# ZB1.net
KiCad netlist of a schematic drawn in Altium Designer
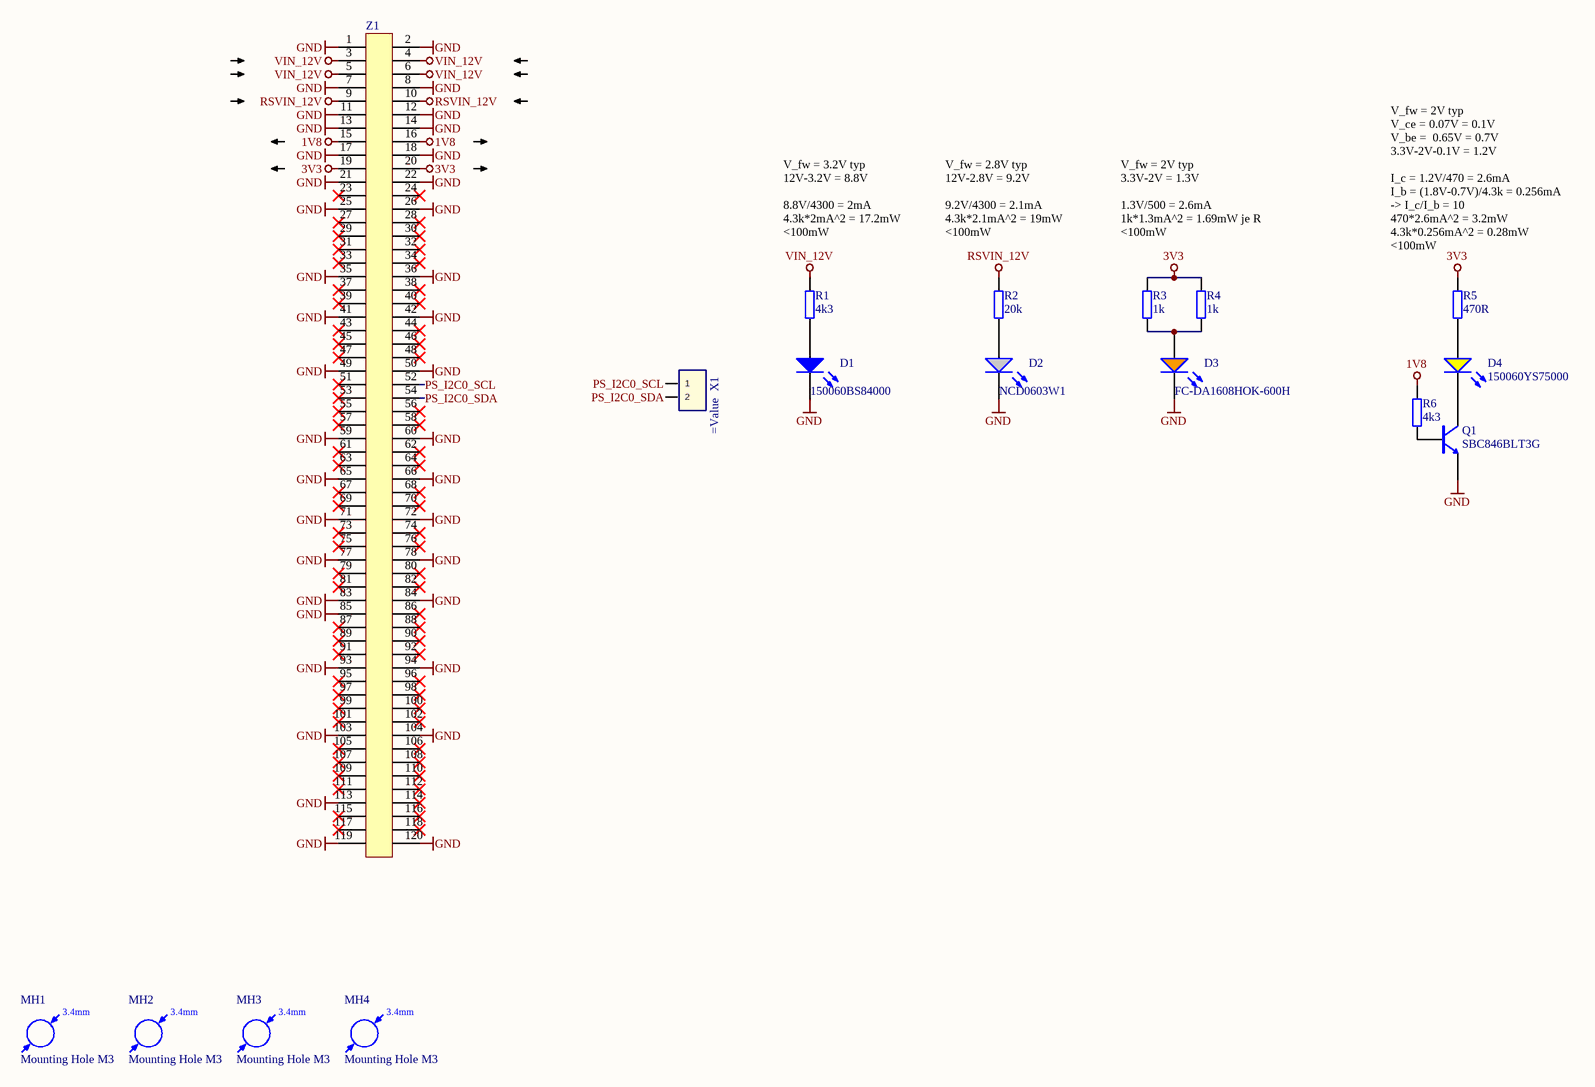
[diagram p0: ZB1.SchDoc]

(export (version "E")
  (design (tool "Eeschema 10.0.6"))
  (components
    (comp (ref "D1")
      (value "150060BS84000")
      (footprint "WL-SMCW_0603")
      (description "WL-SMCW SMD Mono-color Chip LED Waterclear Blue")
      (fields
        (field (name "MANUFACTURER") "Wuerth Elektronik")
        (field (name "LCSC PART NUMBER") "C5197644")
        (field (name "CREATED FROM") "MGremer")
      )
      (libsource (lib "user") (part "LED_Blue"))
    )
    (comp (ref "D2")
      (value "NCD0603W1")
      (footprint "WL-SMCW_0603")
      (description "White light 0603 Light Emitting Diodes (LED) ROHS")
      (fields
        (field (name "MANUFACTURER") "Foshan NationStar Optoelectronics")
        (field (name "LCSC PART NUMBER") "C84265")
        (field (name "CREATED FROM") "NDiringer")
      )
      (libsource (lib "user") (part "LED_White"))
    )
    (comp (ref "D3")
      (value "FC-DA1608HOK-600H")
      (footprint "WL-SMCW_0603")
      (description "LED ORANGE 600~610NM 80~220MCD@20MA TOP VIEW 0603 ROHS")
      (fields
        (field (name "MANUFACTURER") "Foshan NationStar Optoelectronics")
        (field (name "LCSC PART NUMBER") "C84269")
        (field (name "CREATED FROM") "T. Wendt")
      )
      (libsource (lib "user") (part "LED_Amber"))
    )
    (comp (ref "D4")
      (value "150060YS75000")
      (footprint "WL-SMCW_0603")
      (description "LED Yellow 20mA 2V 0603")
      (fields
        (field (name "MANUFACTURER") "Wuerth Elektronik")
        (field (name "LCSC PART NUMBER") "C6784997")
        (field (name "CREATED FROM") "RWeimer")
      )
      (libsource (lib "user") (part "LED_Yellow"))
    )
    (comp (ref "MH1")
      (value "Mounting Hole M3")
      (footprint "MH_3.4")
      (description "Mounting Hole")
      (fields (field (name "CREATED FROM") "MHlatky"))
      (libsource (lib "user") (part "Mounting Hole"))
    )
    (comp (ref "MH2")
      (value "Mounting Hole M3")
      (footprint "MH_3.4")
      (description "Mounting Hole")
      (fields (field (name "CREATED FROM") "MHlatky"))
      (libsource (lib "user") (part "Mounting Hole"))
    )
    (comp (ref "MH3")
      (value "Mounting Hole M3")
      (footprint "MH_3.4")
      (description "Mounting Hole")
      (fields (field (name "CREATED FROM") "MHlatky"))
      (libsource (lib "user") (part "Mounting Hole"))
    )
    (comp (ref "MH4")
      (value "Mounting Hole M3")
      (footprint "MH_3.4")
      (description "Mounting Hole")
      (fields (field (name "CREATED FROM") "MHlatky"))
      (libsource (lib "user") (part "Mounting Hole"))
    )
    (comp (ref "Q1")
      (value "SBC846BLT3G")
      (footprint "SOT-23-3_ONSC")
      (description "Bipolartransistor, NPN 100mA 80V")
      (fields
        (field (name "MANUFACTURER") "onsemi")
        (field (name "LCSC PART NUMBER") "C896883")
        (field (name "CREATED FROM") "RWeimer")
      )
      (libsource (lib "user") (part "NPN-SOT23"))
    )
    (comp (ref "R1")
      (value "4k3")
      (footprint "RES 0603_1608")
      (description "SMD resistor E24 series")
      (fields
        (field (name "MANUFACTURER PART NUMBER") "RK73B1JTTD432J")
        (field (name "MANUFACTURER") "KOA Speer")
        (field (name "CREATED FROM") "MGremer")
      )
      (libsource (lib "user") (part "Resistor"))
    )
    (comp (ref "R2")
      (value "20k")
      (footprint "RES 0603_1608")
      (description "SMD resistor E24 series")
      (fields
        (field (name "MANUFACTURER PART NUMBER") "0603WAF2002T5E")
        (field (name "MANUFACTURER") "UNI-ROYAL")
        (field (name "CREATED FROM") "AGeiger")
      )
      (libsource (lib "user") (part "Resistor"))
    )
    (comp (ref "R3")
      (value "1k")
      (footprint "RES 0603_1608")
      (description "SMD resistor E24 series")
      (fields
        (field (name "MANUFACTURER PART NUMBER") "0603WAF1001T5E")
        (field (name "MANUFACTURER") "UNI-ROYAL")
        (field (name "CREATED FROM") "AGeiger")
      )
      (libsource (lib "user") (part "Resistor"))
    )
    (comp (ref "R4")
      (value "1k")
      (footprint "RES 0603_1608")
      (description "SMD resistor E24 series")
      (fields
        (field (name "MANUFACTURER PART NUMBER") "0603WAF1001T5E")
        (field (name "MANUFACTURER") "UNI-ROYAL")
        (field (name "CREATED FROM") "AGeiger")
      )
      (libsource (lib "user") (part "Resistor"))
    )
    (comp (ref "R5")
      (value "470R")
      (footprint "RES 0603_1608")
      (description "SMD resistor E24 series")
      (fields
        (field (name "MANUFACTURER PART NUMBER") "RK73B1JTTD471J")
        (field (name "MANUFACTURER") "KOA Speer")
        (field (name "CREATED FROM") "MGremer")
      )
      (libsource (lib "user") (part "Resistor"))
    )
    (comp (ref "R6")
      (value "4k3")
      (footprint "RES 0603_1608")
      (description "SMD resistor E24 series")
      (fields
        (field (name "MANUFACTURER PART NUMBER") "RK73B1JTTD432J")
        (field (name "MANUFACTURER") "KOA Speer")
        (field (name "CREATED FROM") "MGremer")
      )
      (libsource (lib "user") (part "Resistor"))
    )
    (comp (ref "X1")
      (value "~")
      (footprint "TSW-102-XX-XXX-S")
      (description "Classic PCB Header Strips, 0.100\" pitch")
      (fields
        (field (name "MANUFACTURER") "SAMTEC")
        (field (name "LCSC PART NUMBER") "C492401")
        (field (name "CREATED BY") "May 18, 2016 - Wendy Xin")
        (field (name "CREATED FROM") "AGeiger")
      )
      (libsource (lib "user") (part "TSW-102-XX-XXX-S"))
    )
    (comp (ref "Z1")
      (value "~")
      (footprint "ERM8-060-02.0-L-DV")
      (description "0.80 mm Edge Rate Rugged High Speed")
      (fields
        (field (name "MANUFACTURER PART NUMBER") "ERM8-060-02.0-L-DV-TR")
        (field (name "MANUFACTURER") "SAMTEC")
        (field (name "CREATED FROM") "AGeiger")
      )
      (libsource (lib "user") (part "CON-120"))
    )
  )
  (nets
    (net (code "1") (name "/PS_I2C0_SCL") (class "Default")
      (node (ref "X1") (pin "1") (pinfunction "1_1") (pintype "passive"))
      (node (ref "Z1") (pin "52") (pinfunction "52_52") (pintype "passive"))
    )
    (net (code "2") (name "/PS_I2C0_SDA") (class "Default")
      (node (ref "X1") (pin "2") (pinfunction "2_2") (pintype "passive"))
      (node (ref "Z1") (pin "54") (pinfunction "54_54") (pintype "passive"))
    )
    (net (code "3") (name "1V8") (class "Default")
      (node (ref "R6") (pin "2") (pinfunction "2_2") (pintype "passive"))
      (node (ref "Z1") (pin "15") (pinfunction "15_15") (pintype "passive"))
      (node (ref "Z1") (pin "16") (pinfunction "16_16") (pintype "passive"))
    )
    (net (code "4") (name "3V3") (class "Default")
      (node (ref "R3") (pin "2") (pinfunction "2_2") (pintype "passive"))
      (node (ref "R4") (pin "2") (pinfunction "2_2") (pintype "passive"))
      (node (ref "R5") (pin "2") (pinfunction "2_2") (pintype "passive"))
      (node (ref "Z1") (pin "19") (pinfunction "19_19") (pintype "passive"))
      (node (ref "Z1") (pin "20") (pinfunction "20_20") (pintype "passive"))
    )
    (net (code "5") (name "GND") (class "Default")
      (node (ref "D1") (pin "1") (pinfunction "K_1") (pintype "passive"))
      (node (ref "D2") (pin "1") (pinfunction "K_1") (pintype "passive"))
      (node (ref "D3") (pin "1") (pinfunction "K_1") (pintype "passive"))
      (node (ref "Q1") (pin "2") (pinfunction "EMITTER_2") (pintype "passive"))
      (node (ref "Z1") (pin "1") (pinfunction "1_1") (pintype "passive"))
      (node (ref "Z1") (pin "103") (pinfunction "103_103") (pintype "passive"))
      (node (ref "Z1") (pin "104") (pinfunction "104_104") (pintype "passive"))
      (node (ref "Z1") (pin "11") (pinfunction "11_11") (pintype "passive"))
      (node (ref "Z1") (pin "113") (pinfunction "113_113") (pintype "passive"))
      (node (ref "Z1") (pin "119") (pinfunction "119_119") (pintype "passive"))
      (node (ref "Z1") (pin "12") (pinfunction "12_12") (pintype "passive"))
      (node (ref "Z1") (pin "120") (pinfunction "120_120") (pintype "passive"))
      (node (ref "Z1") (pin "13") (pinfunction "13_13") (pintype "passive"))
      (node (ref "Z1") (pin "14") (pinfunction "14_14") (pintype "passive"))
      (node (ref "Z1") (pin "17") (pinfunction "17_17") (pintype "passive"))
      (node (ref "Z1") (pin "18") (pinfunction "18_18") (pintype "passive"))
      (node (ref "Z1") (pin "2") (pinfunction "2_2") (pintype "passive"))
      (node (ref "Z1") (pin "21") (pinfunction "21_21") (pintype "passive"))
      (node (ref "Z1") (pin "22") (pinfunction "22_22") (pintype "passive"))
      (node (ref "Z1") (pin "25") (pinfunction "25_25") (pintype "passive"))
      (node (ref "Z1") (pin "26") (pinfunction "26_26") (pintype "passive"))
      (node (ref "Z1") (pin "35") (pinfunction "35_35") (pintype "passive"))
      (node (ref "Z1") (pin "36") (pinfunction "36_36") (pintype "passive"))
      (node (ref "Z1") (pin "41") (pinfunction "41_41") (pintype "passive"))
      (node (ref "Z1") (pin "42") (pinfunction "42_42") (pintype "passive"))
      (node (ref "Z1") (pin "49") (pinfunction "49_49") (pintype "passive"))
      (node (ref "Z1") (pin "50") (pinfunction "50_50") (pintype "passive"))
      (node (ref "Z1") (pin "59") (pinfunction "59_59") (pintype "passive"))
      (node (ref "Z1") (pin "60") (pinfunction "60_60") (pintype "passive"))
      (node (ref "Z1") (pin "65") (pinfunction "65_65") (pintype "passive"))
      (node (ref "Z1") (pin "66") (pinfunction "66_66") (pintype "passive"))
      (node (ref "Z1") (pin "7") (pinfunction "7_7") (pintype "passive"))
      (node (ref "Z1") (pin "71") (pinfunction "71_71") (pintype "passive"))
      (node (ref "Z1") (pin "72") (pinfunction "72_72") (pintype "passive"))
      (node (ref "Z1") (pin "77") (pinfunction "77_77") (pintype "passive"))
      (node (ref "Z1") (pin "78") (pinfunction "78_78") (pintype "passive"))
      (node (ref "Z1") (pin "8") (pinfunction "8_8") (pintype "passive"))
      (node (ref "Z1") (pin "83") (pinfunction "83_83") (pintype "passive"))
      (node (ref "Z1") (pin "84") (pinfunction "84_84") (pintype "passive"))
      (node (ref "Z1") (pin "85") (pinfunction "85_85") (pintype "passive"))
      (node (ref "Z1") (pin "93") (pinfunction "93_93") (pintype "passive"))
      (node (ref "Z1") (pin "94") (pinfunction "94_94") (pintype "passive"))
    )
    (net (code "6") (name "Net-(D1-A)") (class "Default")
      (node (ref "D1") (pin "2") (pinfunction "A_2") (pintype "passive"))
      (node (ref "R1") (pin "1") (pinfunction "1_1") (pintype "passive"))
    )
    (net (code "7") (name "Net-(D2-A)") (class "Default")
      (node (ref "D2") (pin "2") (pinfunction "A_2") (pintype "passive"))
      (node (ref "R2") (pin "1") (pinfunction "1_1") (pintype "passive"))
    )
    (net (code "8") (name "Net-(D3-A)") (class "Default")
      (node (ref "D3") (pin "2") (pinfunction "A_2") (pintype "passive"))
      (node (ref "R3") (pin "1") (pinfunction "1_1") (pintype "passive"))
      (node (ref "R4") (pin "1") (pinfunction "1_1") (pintype "passive"))
    )
    (net (code "9") (name "Net-(D4-A)") (class "Default")
      (node (ref "D4") (pin "2") (pinfunction "A_2") (pintype "passive"))
      (node (ref "R5") (pin "1") (pinfunction "1_1") (pintype "passive"))
    )
    (net (code "10") (name "Net-(D4-K)") (class "Default")
      (node (ref "D4") (pin "1") (pinfunction "K_1") (pintype "passive"))
      (node (ref "Q1") (pin "3") (pinfunction "COLLECTOR_3") (pintype "passive"))
    )
    (net (code "11") (name "Net-(Q1-BASIS)") (class "Default")
      (node (ref "Q1") (pin "1") (pinfunction "BASIS_1") (pintype "passive"))
      (node (ref "R6") (pin "1") (pinfunction "1_1") (pintype "passive"))
    )
    (net (code "12") (name "RSVIN_12V") (class "Default")
      (node (ref "R2") (pin "2") (pinfunction "2_2") (pintype "passive"))
      (node (ref "Z1") (pin "10") (pinfunction "10_10") (pintype "passive"))
      (node (ref "Z1") (pin "9") (pinfunction "9_9") (pintype "passive"))
    )
    (net (code "13") (name "VIN_12V") (class "Default")
      (node (ref "R1") (pin "2") (pinfunction "2_2") (pintype "passive"))
      (node (ref "Z1") (pin "3") (pinfunction "3_3") (pintype "passive"))
      (node (ref "Z1") (pin "4") (pinfunction "4_4") (pintype "passive"))
      (node (ref "Z1") (pin "5") (pinfunction "5_5") (pintype "passive"))
      (node (ref "Z1") (pin "6") (pinfunction "6_6") (pintype "passive"))
    )
    (net (code "14") (name "unconnected-(Z1-Pad23)") (class "Default")
      (node (ref "Z1") (pin "23") (pinfunction "23_23") (pintype "passive+no_connect"))
    )
    (net (code "15") (name "unconnected-(Z1-Pad24)") (class "Default")
      (node (ref "Z1") (pin "24") (pinfunction "24_24") (pintype "passive+no_connect"))
    )
    (net (code "16") (name "unconnected-(Z1-Pad27)") (class "Default")
      (node (ref "Z1") (pin "27") (pinfunction "27_27") (pintype "passive+no_connect"))
    )
    (net (code "17") (name "unconnected-(Z1-Pad28)") (class "Default")
      (node (ref "Z1") (pin "28") (pinfunction "28_28") (pintype "passive+no_connect"))
    )
    (net (code "18") (name "unconnected-(Z1-Pad29)") (class "Default")
      (node (ref "Z1") (pin "29") (pinfunction "29_29") (pintype "passive+no_connect"))
    )
    (net (code "19") (name "unconnected-(Z1-Pad30)") (class "Default")
      (node (ref "Z1") (pin "30") (pinfunction "30_30") (pintype "passive+no_connect"))
    )
    (net (code "20") (name "unconnected-(Z1-Pad31)") (class "Default")
      (node (ref "Z1") (pin "31") (pinfunction "31_31") (pintype "passive+no_connect"))
    )
    (net (code "21") (name "unconnected-(Z1-Pad32)") (class "Default")
      (node (ref "Z1") (pin "32") (pinfunction "32_32") (pintype "passive+no_connect"))
    )
    (net (code "22") (name "unconnected-(Z1-Pad33)") (class "Default")
      (node (ref "Z1") (pin "33") (pinfunction "33_33") (pintype "passive+no_connect"))
    )
    (net (code "23") (name "unconnected-(Z1-Pad34)") (class "Default")
      (node (ref "Z1") (pin "34") (pinfunction "34_34") (pintype "passive+no_connect"))
    )
    (net (code "24") (name "unconnected-(Z1-Pad37)") (class "Default")
      (node (ref "Z1") (pin "37") (pinfunction "37_37") (pintype "passive+no_connect"))
    )
    (net (code "25") (name "unconnected-(Z1-Pad38)") (class "Default")
      (node (ref "Z1") (pin "38") (pinfunction "38_38") (pintype "passive+no_connect"))
    )
    (net (code "26") (name "unconnected-(Z1-Pad39)") (class "Default")
      (node (ref "Z1") (pin "39") (pinfunction "39_39") (pintype "passive+no_connect"))
    )
    (net (code "27") (name "unconnected-(Z1-Pad40)") (class "Default")
      (node (ref "Z1") (pin "40") (pinfunction "40_40") (pintype "passive+no_connect"))
    )
    (net (code "28") (name "unconnected-(Z1-Pad43)") (class "Default")
      (node (ref "Z1") (pin "43") (pinfunction "43_43") (pintype "passive+no_connect"))
    )
    (net (code "29") (name "unconnected-(Z1-Pad44)") (class "Default")
      (node (ref "Z1") (pin "44") (pinfunction "44_44") (pintype "passive+no_connect"))
    )
    (net (code "30") (name "unconnected-(Z1-Pad45)") (class "Default")
      (node (ref "Z1") (pin "45") (pinfunction "45_45") (pintype "passive+no_connect"))
    )
    (net (code "31") (name "unconnected-(Z1-Pad46)") (class "Default")
      (node (ref "Z1") (pin "46") (pinfunction "46_46") (pintype "passive+no_connect"))
    )
    (net (code "32") (name "unconnected-(Z1-Pad47)") (class "Default")
      (node (ref "Z1") (pin "47") (pinfunction "47_47") (pintype "passive+no_connect"))
    )
    (net (code "33") (name "unconnected-(Z1-Pad48)") (class "Default")
      (node (ref "Z1") (pin "48") (pinfunction "48_48") (pintype "passive+no_connect"))
    )
    (net (code "34") (name "unconnected-(Z1-Pad51)") (class "Default")
      (node (ref "Z1") (pin "51") (pinfunction "51_51") (pintype "passive+no_connect"))
    )
    (net (code "35") (name "unconnected-(Z1-Pad53)") (class "Default")
      (node (ref "Z1") (pin "53") (pinfunction "53_53") (pintype "passive+no_connect"))
    )
    (net (code "36") (name "unconnected-(Z1-Pad55)") (class "Default")
      (node (ref "Z1") (pin "55") (pinfunction "55_55") (pintype "passive+no_connect"))
    )
    (net (code "37") (name "unconnected-(Z1-Pad56)") (class "Default")
      (node (ref "Z1") (pin "56") (pinfunction "56_56") (pintype "passive+no_connect"))
    )
    (net (code "38") (name "unconnected-(Z1-Pad57)") (class "Default")
      (node (ref "Z1") (pin "57") (pinfunction "57_57") (pintype "passive+no_connect"))
    )
    (net (code "39") (name "unconnected-(Z1-Pad58)") (class "Default")
      (node (ref "Z1") (pin "58") (pinfunction "58_58") (pintype "passive+no_connect"))
    )
    (net (code "40") (name "unconnected-(Z1-Pad61)") (class "Default")
      (node (ref "Z1") (pin "61") (pinfunction "61_61") (pintype "passive+no_connect"))
    )
    (net (code "41") (name "unconnected-(Z1-Pad62)") (class "Default")
      (node (ref "Z1") (pin "62") (pinfunction "62_62") (pintype "passive+no_connect"))
    )
    (net (code "42") (name "unconnected-(Z1-Pad63)") (class "Default")
      (node (ref "Z1") (pin "63") (pinfunction "63_63") (pintype "passive+no_connect"))
    )
    (net (code "43") (name "unconnected-(Z1-Pad64)") (class "Default")
      (node (ref "Z1") (pin "64") (pinfunction "64_64") (pintype "passive+no_connect"))
    )
    (net (code "44") (name "unconnected-(Z1-Pad67)") (class "Default")
      (node (ref "Z1") (pin "67") (pinfunction "67_67") (pintype "passive+no_connect"))
    )
    (net (code "45") (name "unconnected-(Z1-Pad68)") (class "Default")
      (node (ref "Z1") (pin "68") (pinfunction "68_68") (pintype "passive+no_connect"))
    )
    (net (code "46") (name "unconnected-(Z1-Pad69)") (class "Default")
      (node (ref "Z1") (pin "69") (pinfunction "69_69") (pintype "passive+no_connect"))
    )
    (net (code "47") (name "unconnected-(Z1-Pad70)") (class "Default")
      (node (ref "Z1") (pin "70") (pinfunction "70_70") (pintype "passive+no_connect"))
    )
    (net (code "48") (name "unconnected-(Z1-Pad73)") (class "Default")
      (node (ref "Z1") (pin "73") (pinfunction "73_73") (pintype "passive+no_connect"))
    )
    (net (code "49") (name "unconnected-(Z1-Pad74)") (class "Default")
      (node (ref "Z1") (pin "74") (pinfunction "74_74") (pintype "passive+no_connect"))
    )
    (net (code "50") (name "unconnected-(Z1-Pad75)") (class "Default")
      (node (ref "Z1") (pin "75") (pinfunction "75_75") (pintype "passive+no_connect"))
    )
    (net (code "51") (name "unconnected-(Z1-Pad76)") (class "Default")
      (node (ref "Z1") (pin "76") (pinfunction "76_76") (pintype "passive+no_connect"))
    )
    (net (code "52") (name "unconnected-(Z1-Pad79)") (class "Default")
      (node (ref "Z1") (pin "79") (pinfunction "79_79") (pintype "passive+no_connect"))
    )
    (net (code "53") (name "unconnected-(Z1-Pad80)") (class "Default")
      (node (ref "Z1") (pin "80") (pinfunction "80_80") (pintype "passive+no_connect"))
    )
    (net (code "54") (name "unconnected-(Z1-Pad81)") (class "Default")
      (node (ref "Z1") (pin "81") (pinfunction "81_81") (pintype "passive+no_connect"))
    )
    (net (code "55") (name "unconnected-(Z1-Pad82)") (class "Default")
      (node (ref "Z1") (pin "82") (pinfunction "82_82") (pintype "passive+no_connect"))
    )
    (net (code "56") (name "unconnected-(Z1-Pad86)") (class "Default")
      (node (ref "Z1") (pin "86") (pinfunction "86_86") (pintype "passive+no_connect"))
    )
    (net (code "57") (name "unconnected-(Z1-Pad87)") (class "Default")
      (node (ref "Z1") (pin "87") (pinfunction "87_87") (pintype "passive+no_connect"))
    )
    (net (code "58") (name "unconnected-(Z1-Pad88)") (class "Default")
      (node (ref "Z1") (pin "88") (pinfunction "88_88") (pintype "passive+no_connect"))
    )
    (net (code "59") (name "unconnected-(Z1-Pad89)") (class "Default")
      (node (ref "Z1") (pin "89") (pinfunction "89_89") (pintype "passive+no_connect"))
    )
    (net (code "60") (name "unconnected-(Z1-Pad90)") (class "Default")
      (node (ref "Z1") (pin "90") (pinfunction "90_90") (pintype "passive+no_connect"))
    )
    (net (code "61") (name "unconnected-(Z1-Pad91)") (class "Default")
      (node (ref "Z1") (pin "91") (pinfunction "91_91") (pintype "passive+no_connect"))
    )
    (net (code "62") (name "unconnected-(Z1-Pad92)") (class "Default")
      (node (ref "Z1") (pin "92") (pinfunction "92_92") (pintype "passive+no_connect"))
    )
    (net (code "63") (name "unconnected-(Z1-Pad95)") (class "Default")
      (node (ref "Z1") (pin "95") (pinfunction "95_95") (pintype "passive+no_connect"))
    )
    (net (code "64") (name "unconnected-(Z1-Pad96)") (class "Default")
      (node (ref "Z1") (pin "96") (pinfunction "96_96") (pintype "passive+no_connect"))
    )
    (net (code "65") (name "unconnected-(Z1-Pad97)") (class "Default")
      (node (ref "Z1") (pin "97") (pinfunction "97_97") (pintype "passive+no_connect"))
    )
    (net (code "66") (name "unconnected-(Z1-Pad98)") (class "Default")
      (node (ref "Z1") (pin "98") (pinfunction "98_98") (pintype "passive+no_connect"))
    )
    (net (code "67") (name "unconnected-(Z1-Pad99)") (class "Default")
      (node (ref "Z1") (pin "99") (pinfunction "99_99") (pintype "passive+no_connect"))
    )
    (net (code "68") (name "unconnected-(Z1-Pad100)") (class "Default")
      (node (ref "Z1") (pin "100") (pinfunction "100_100") (pintype "passive+no_connect"))
    )
    (net (code "69") (name "unconnected-(Z1-Pad101)") (class "Default")
      (node (ref "Z1") (pin "101") (pinfunction "101_101") (pintype "passive+no_connect"))
    )
    (net (code "70") (name "unconnected-(Z1-Pad102)") (class "Default")
      (node (ref "Z1") (pin "102") (pinfunction "102_102") (pintype "passive+no_connect"))
    )
    (net (code "71") (name "unconnected-(Z1-Pad105)") (class "Default")
      (node (ref "Z1") (pin "105") (pinfunction "105_105") (pintype "passive+no_connect"))
    )
    (net (code "72") (name "unconnected-(Z1-Pad106)") (class "Default")
      (node (ref "Z1") (pin "106") (pinfunction "106_106") (pintype "passive+no_connect"))
    )
    (net (code "73") (name "unconnected-(Z1-Pad107)") (class "Default")
      (node (ref "Z1") (pin "107") (pinfunction "107_107") (pintype "passive+no_connect"))
    )
    (net (code "74") (name "unconnected-(Z1-Pad108)") (class "Default")
      (node (ref "Z1") (pin "108") (pinfunction "108_108") (pintype "passive+no_connect"))
    )
    (net (code "75") (name "unconnected-(Z1-Pad109)") (class "Default")
      (node (ref "Z1") (pin "109") (pinfunction "109_109") (pintype "passive+no_connect"))
    )
    (net (code "76") (name "unconnected-(Z1-Pad110)") (class "Default")
      (node (ref "Z1") (pin "110") (pinfunction "110_110") (pintype "passive+no_connect"))
    )
    (net (code "77") (name "unconnected-(Z1-Pad111)") (class "Default")
      (node (ref "Z1") (pin "111") (pinfunction "111_111") (pintype "passive+no_connect"))
    )
    (net (code "78") (name "unconnected-(Z1-Pad112)") (class "Default")
      (node (ref "Z1") (pin "112") (pinfunction "112_112") (pintype "passive+no_connect"))
    )
    (net (code "79") (name "unconnected-(Z1-Pad114)") (class "Default")
      (node (ref "Z1") (pin "114") (pinfunction "114_114") (pintype "passive+no_connect"))
    )
    (net (code "80") (name "unconnected-(Z1-Pad115)") (class "Default")
      (node (ref "Z1") (pin "115") (pinfunction "115_115") (pintype "passive+no_connect"))
    )
    (net (code "81") (name "unconnected-(Z1-Pad116)") (class "Default")
      (node (ref "Z1") (pin "116") (pinfunction "116_116") (pintype "passive+no_connect"))
    )
    (net (code "82") (name "unconnected-(Z1-Pad117)") (class "Default")
      (node (ref "Z1") (pin "117") (pinfunction "117_117") (pintype "passive+no_connect"))
    )
    (net (code "83") (name "unconnected-(Z1-Pad118)") (class "Default")
      (node (ref "Z1") (pin "118") (pinfunction "118_118") (pintype "passive+no_connect"))
    )
  )
)
